# TouchPad-HatchedGround.net
KiCad netlist of a schematic drawn in EAGLE
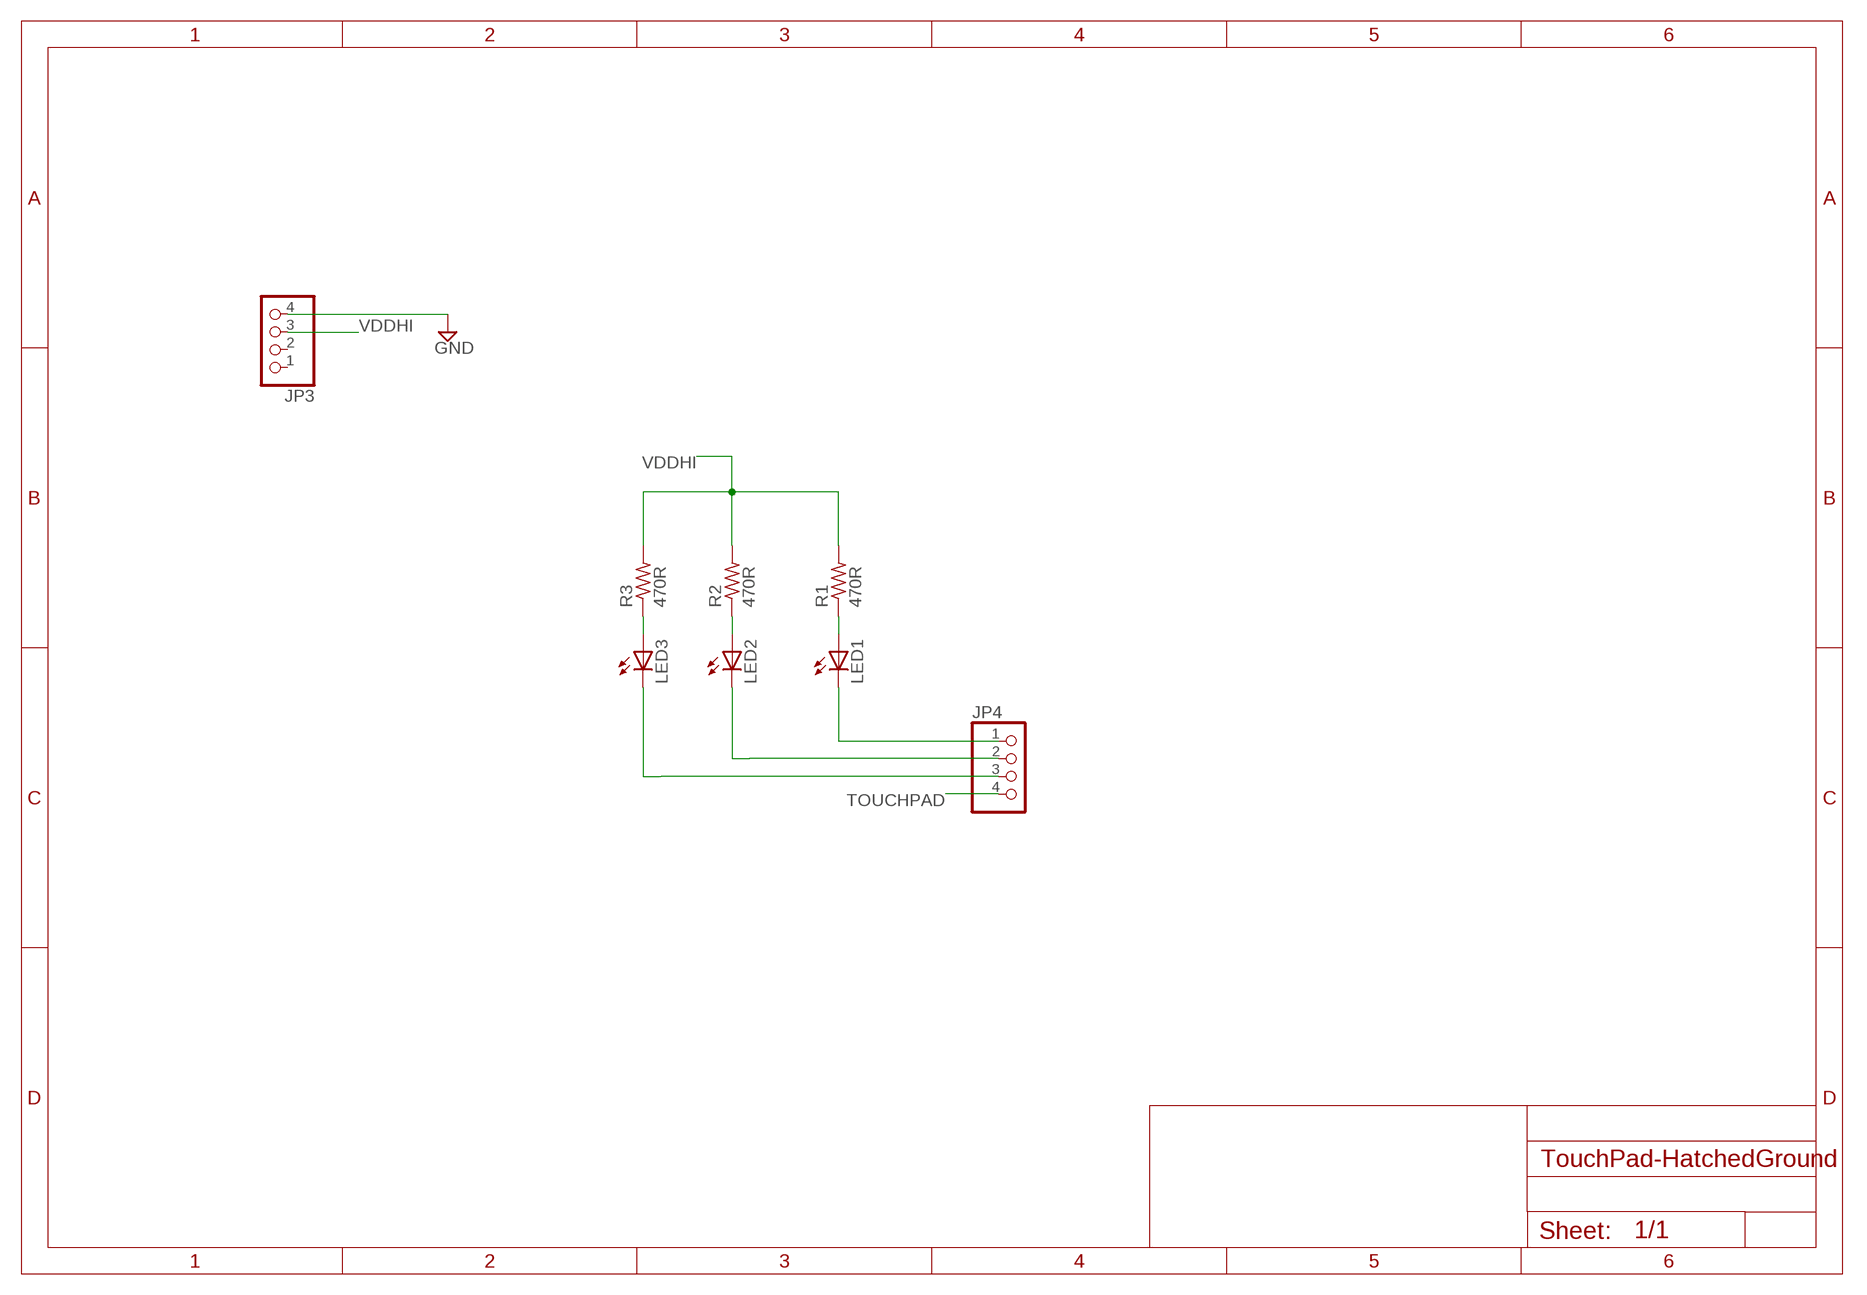
[diagram p0: schematic, sheet 1]

(export (version "E")
  (design (tool "Eeschema 10.0.6"))
  (components
    (comp (ref "JP3")
      (value "PINHD-1X4")
      (footprint "eagle-import:1X04")
      (libsource (lib "eagle-import") (part "PINHD-1X4"))
    )
    (comp (ref "JP4")
      (value "PINHD-1X4")
      (footprint "eagle-import:1X04")
      (libsource (lib "eagle-import") (part "PINHD-1X4"))
    )
    (comp (ref "LED1")
      (value "LEDCHIPLED_1206")
      (footprint "eagle-import:CHIPLED_1206")
      (libsource (lib "eagle-import") (part "LEDCHIPLED_1206"))
    )
    (comp (ref "LED2")
      (value "LEDCHIPLED_1206")
      (footprint "eagle-import:CHIPLED_1206")
      (libsource (lib "eagle-import") (part "LEDCHIPLED_1206"))
    )
    (comp (ref "LED3")
      (value "LEDCHIPLED_1206")
      (footprint "eagle-import:CHIPLED_1206")
      (libsource (lib "eagle-import") (part "LEDCHIPLED_1206"))
    )
    (comp (ref "R1")
      (value "470R")
      (footprint "eagle-import:R0603")
      (libsource (lib "eagle-import") (part "R-US_R0603"))
    )
    (comp (ref "R2")
      (value "470R")
      (footprint "eagle-import:R0603")
      (libsource (lib "eagle-import") (part "R-US_R0603"))
    )
    (comp (ref "R3")
      (value "470R")
      (footprint "eagle-import:R0603")
      (libsource (lib "eagle-import") (part "R-US_R0603"))
    )
  )
  (nets
    (net (code "1") (name "/TOUCHPAD") (class "Default")
      (node (ref "JP4") (pin "4") (pinfunction "4_4") (pintype "passive"))
    )
    (net (code "2") (name "/VDDHI") (class "Default")
      (node (ref "JP3") (pin "3") (pinfunction "3_3") (pintype "passive"))
      (node (ref "R1") (pin "2") (pinfunction "2_2") (pintype "passive"))
      (node (ref "R2") (pin "2") (pinfunction "2_2") (pintype "passive"))
      (node (ref "R3") (pin "2") (pinfunction "2_2") (pintype "passive"))
    )
    (net (code "3") (name "GND") (class "Default")
      (node (ref "JP3") (pin "4") (pinfunction "4_4") (pintype "passive"))
    )
    (net (code "4") (name "Net-(JP4-Pad1)") (class "Default")
      (node (ref "JP4") (pin "1") (pinfunction "1_1") (pintype "passive"))
      (node (ref "LED1") (pin "C") (pinfunction "C_C") (pintype "passive"))
    )
    (net (code "5") (name "Net-(JP4-Pad2)") (class "Default")
      (node (ref "JP4") (pin "2") (pinfunction "2_2") (pintype "passive"))
      (node (ref "LED2") (pin "C") (pinfunction "C_C") (pintype "passive"))
    )
    (net (code "6") (name "Net-(JP4-Pad3)") (class "Default")
      (node (ref "JP4") (pin "3") (pinfunction "3_3") (pintype "passive"))
      (node (ref "LED3") (pin "C") (pinfunction "C_C") (pintype "passive"))
    )
    (net (code "7") (name "Net-(LED1-PadA)") (class "Default")
      (node (ref "LED1") (pin "A") (pinfunction "A_A") (pintype "passive"))
      (node (ref "R1") (pin "1") (pinfunction "1_1") (pintype "passive"))
    )
    (net (code "8") (name "Net-(LED2-PadA)") (class "Default")
      (node (ref "LED2") (pin "A") (pinfunction "A_A") (pintype "passive"))
      (node (ref "R2") (pin "1") (pinfunction "1_1") (pintype "passive"))
    )
    (net (code "9") (name "Net-(LED3-PadA)") (class "Default")
      (node (ref "LED3") (pin "A") (pinfunction "A_A") (pintype "passive"))
      (node (ref "R3") (pin "1") (pinfunction "1_1") (pintype "passive"))
    )
    (net (code "10") (name "unconnected-(JP3-Pad1)") (class "Default")
      (node (ref "JP3") (pin "1") (pinfunction "1_1") (pintype "passive"))
    )
    (net (code "11") (name "unconnected-(JP3-Pad2)") (class "Default")
      (node (ref "JP3") (pin "2") (pinfunction "2_2") (pintype "passive"))
    )
  )
)
